# badge_mil.net
KiCad netlist of a schematic drawn in EAGLE
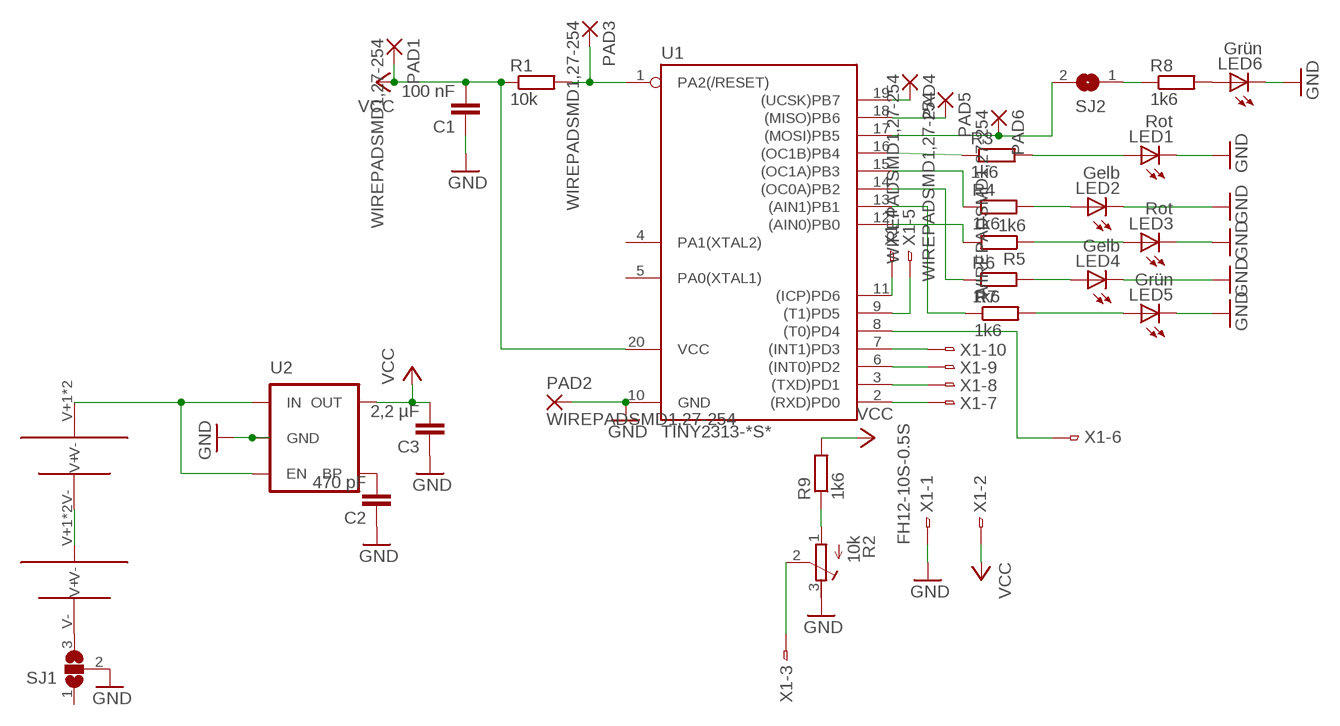
[diagram p0: schematic, sheet 1]

(export (version "E")
  (design (tool "Eeschema 10.0.6"))
  (components
    (comp (ref "C1")
      (value "100 nF")
      (footprint "eagle-import:C0805")
      (libsource (lib "eagle-import") (part "C-EUC0805"))
    )
    (comp (ref "C2")
      (value "470 pF")
      (footprint "eagle-import:C0805")
      (libsource (lib "eagle-import") (part "C-EUC0805"))
    )
    (comp (ref "C3")
      (value "2,2 µF")
      (footprint "eagle-import:C0805")
      (libsource (lib "eagle-import") (part "C-EUC0805"))
    )
    (comp (ref "LED1")
      (value "Rot")
      (footprint "eagle-import:SML0603")
      (libsource (lib "eagle-import") (part "LEDSML0603"))
    )
    (comp (ref "LED2")
      (value "Gelb")
      (footprint "eagle-import:SML0603")
      (libsource (lib "eagle-import") (part "LEDSML0603"))
    )
    (comp (ref "LED3")
      (value "Rot")
      (footprint "eagle-import:SML0603")
      (libsource (lib "eagle-import") (part "LEDSML0603"))
    )
    (comp (ref "LED4")
      (value "Gelb")
      (footprint "eagle-import:SML0603")
      (libsource (lib "eagle-import") (part "LEDSML0603"))
    )
    (comp (ref "LED5")
      (value "Grün")
      (footprint "eagle-import:SML0603")
      (libsource (lib "eagle-import") (part "LEDSML0603"))
    )
    (comp (ref "LED6")
      (value "Grün")
      (footprint "eagle-import:SML0603")
      (libsource (lib "eagle-import") (part "LEDSML0603"))
    )
    (comp (ref "PAD1")
      (value "WIREPADSMD1,27-254")
      (footprint "eagle-import:SMD1,27-2,54")
      (libsource (lib "eagle-import") (part "WIREPADSMD1,27-254"))
    )
    (comp (ref "PAD2")
      (value "WIREPADSMD1,27-254")
      (footprint "eagle-import:SMD1,27-2,54")
      (libsource (lib "eagle-import") (part "WIREPADSMD1,27-254"))
    )
    (comp (ref "PAD3")
      (value "WIREPADSMD1,27-254")
      (footprint "eagle-import:SMD1,27-2,54")
      (libsource (lib "eagle-import") (part "WIREPADSMD1,27-254"))
    )
    (comp (ref "PAD4")
      (value "WIREPADSMD1,27-254")
      (footprint "eagle-import:SMD1,27-2,54")
      (libsource (lib "eagle-import") (part "WIREPADSMD1,27-254"))
    )
    (comp (ref "PAD5")
      (value "WIREPADSMD1,27-254")
      (footprint "eagle-import:SMD1,27-2,54")
      (libsource (lib "eagle-import") (part "WIREPADSMD1,27-254"))
    )
    (comp (ref "PAD6")
      (value "WIREPADSMD1,27-254")
      (footprint "eagle-import:SMD1,27-2,54")
      (libsource (lib "eagle-import") (part "WIREPADSMD1,27-254"))
    )
    (comp (ref "R1")
      (value "10k")
      (footprint "eagle-import:R0805")
      (libsource (lib "eagle-import") (part "R-EU_R0805"))
    )
    (comp (ref "R2")
      (value "10k")
      (footprint "eagle-import:RTRIM4G_J")
      (libsource (lib "eagle-import") (part "R-TRIMM4G/J"))
    )
    (comp (ref "R3")
      (value "1k6")
      (footprint "eagle-import:R0805")
      (libsource (lib "eagle-import") (part "R-EU_R0805"))
    )
    (comp (ref "R4")
      (value "1k6")
      (footprint "eagle-import:R0805")
      (libsource (lib "eagle-import") (part "R-EU_R0805"))
    )
    (comp (ref "R5")
      (value "1k6")
      (footprint "eagle-import:R0805")
      (libsource (lib "eagle-import") (part "R-EU_R0805"))
    )
    (comp (ref "R6")
      (value "1k6")
      (footprint "eagle-import:R0805")
      (libsource (lib "eagle-import") (part "R-EU_R0805"))
    )
    (comp (ref "R7")
      (value "1k6")
      (footprint "eagle-import:R0805")
      (libsource (lib "eagle-import") (part "R-EU_R0805"))
    )
    (comp (ref "R8")
      (value "1k6")
      (footprint "eagle-import:R0805")
      (libsource (lib "eagle-import") (part "R-EU_R0805"))
    )
    (comp (ref "R9")
      (value "1k6")
      (footprint "eagle-import:R0805")
      (libsource (lib "eagle-import") (part "R-EU_R0805"))
    )
    (comp (ref "SJ1")
      (value "SJ2WW")
      (footprint "eagle-import:SJ_2W")
      (libsource (lib "eagle-import") (part "SJ2WW"))
    )
    (comp (ref "SJ2")
      (value "SJW")
      (footprint "eagle-import:SJW")
      (libsource (lib "eagle-import") (part "SJW"))
    )
    (comp (ref "U$1")
      (value "KEYSTONE3002")
      (footprint "eagle-import:KEYSTONE3002")
      (libsource (lib "eagle-import") (part "KEYSTONE3002"))
    )
    (comp (ref "U$2")
      (value "KEYSTONE3002")
      (footprint "eagle-import:KEYSTONE3002")
      (libsource (lib "eagle-import") (part "KEYSTONE3002"))
    )
    (comp (ref "U1")
      (value "TINY2313-*S*")
      (footprint "eagle-import:SO20L$")
      (libsource (lib "eagle-import") (part "TINY2313-S"))
    )
    (comp (ref "U2")
      (value "MIC52055V")
      (footprint "eagle-import:SOT23-5")
      (libsource (lib "eagle-import") (part "MIC52055V"))
    )
    (comp (ref "X1")
      (value "FH12-10S-0.5S")
      (footprint "eagle-import:FH12-10S-1.0SH")
      (libsource (lib "eagle-import") (part "FH12-10S-0.5S"))
    )
  )
  (nets
    (net (code "1") (name "GND") (class "Default")
      (node (ref "C1") (pin "1") (pinfunction "1_1") (pintype "passive"))
      (node (ref "C2") (pin "1") (pinfunction "1_1") (pintype "passive"))
      (node (ref "C3") (pin "1") (pinfunction "1_1") (pintype "passive"))
      (node (ref "LED1") (pin "C") (pinfunction "C_C") (pintype "passive"))
      (node (ref "LED2") (pin "C") (pinfunction "C_C") (pintype "passive"))
      (node (ref "LED3") (pin "C") (pinfunction "C_C") (pintype "passive"))
      (node (ref "LED4") (pin "C") (pinfunction "C_C") (pintype "passive"))
      (node (ref "LED5") (pin "C") (pinfunction "C_C") (pintype "passive"))
      (node (ref "LED6") (pin "C") (pinfunction "C_C") (pintype "passive"))
      (node (ref "PAD2") (pin "1") (pinfunction "P_1") (pintype "passive"))
      (node (ref "R2") (pin "3") (pinfunction "A_3") (pintype "passive"))
      (node (ref "SJ1") (pin "2") (pinfunction "2_2") (pintype "passive"))
      (node (ref "U1") (pin "10") (pinfunction "GND_10") (pintype "power_in"))
      (node (ref "U2") (pin "2") (pinfunction "GND_2") (pintype "input"))
      (node (ref "X1") (pin "1") (pinfunction "1_1") (pintype "passive"))
    )
    (net (code "2") (name "Net-(LED1-PadA)") (class "Default")
      (node (ref "LED1") (pin "A") (pinfunction "A_A") (pintype "passive"))
      (node (ref "R3") (pin "2") (pinfunction "2_2") (pintype "passive"))
    )
    (net (code "3") (name "Net-(LED2-PadA)") (class "Default")
      (node (ref "LED2") (pin "A") (pinfunction "A_A") (pintype "passive"))
      (node (ref "R4") (pin "2") (pinfunction "2_2") (pintype "passive"))
    )
    (net (code "4") (name "Net-(LED3-PadA)") (class "Default")
      (node (ref "LED3") (pin "A") (pinfunction "A_A") (pintype "passive"))
      (node (ref "R5") (pin "1") (pinfunction "1_1") (pintype "passive"))
    )
    (net (code "5") (name "Net-(LED4-PadA)") (class "Default")
      (node (ref "LED4") (pin "A") (pinfunction "A_A") (pintype "passive"))
      (node (ref "R6") (pin "2") (pinfunction "2_2") (pintype "passive"))
    )
    (net (code "6") (name "Net-(LED5-PadA)") (class "Default")
      (node (ref "LED5") (pin "A") (pinfunction "A_A") (pintype "passive"))
      (node (ref "R7") (pin "2") (pinfunction "2_2") (pintype "passive"))
    )
    (net (code "7") (name "Net-(LED6-PadA)") (class "Default")
      (node (ref "LED6") (pin "A") (pinfunction "A_A") (pintype "passive"))
      (node (ref "R8") (pin "2") (pinfunction "2_2") (pintype "passive"))
    )
    (net (code "8") (name "Net-(PAD3-P)") (class "Default")
      (node (ref "PAD3") (pin "1") (pinfunction "P_1") (pintype "passive"))
      (node (ref "R1") (pin "2") (pinfunction "2_2") (pintype "passive"))
      (node (ref "U1") (pin "1") (pinfunction "PA2(/RESET)_1") (pintype "input"))
    )
    (net (code "9") (name "Net-(PAD4-P)") (class "Default")
      (node (ref "PAD4") (pin "1") (pinfunction "P_1") (pintype "passive"))
      (node (ref "U1") (pin "19") (pinfunction "(UCSK)PB7_19") (pintype "bidirectional"))
    )
    (net (code "10") (name "Net-(PAD5-P)") (class "Default")
      (node (ref "PAD5") (pin "1") (pinfunction "P_1") (pintype "passive"))
      (node (ref "U1") (pin "18") (pinfunction "(MISO)PB6_18") (pintype "bidirectional"))
    )
    (net (code "11") (name "Net-(PAD6-P)") (class "Default")
      (node (ref "PAD6") (pin "1") (pinfunction "P_1") (pintype "passive"))
      (node (ref "SJ2") (pin "2") (pinfunction "2_2") (pintype "passive"))
      (node (ref "U1") (pin "17") (pinfunction "(MOSI)PB5_17") (pintype "bidirectional"))
    )
    (net (code "12") (name "Net-(R2-E)") (class "Default")
      (node (ref "R2") (pin "1") (pinfunction "E_1") (pintype "passive"))
      (node (ref "R9") (pin "1") (pinfunction "1_1") (pintype "passive"))
    )
    (net (code "13") (name "Net-(R2-S)") (class "Default")
      (node (ref "R2") (pin "2") (pinfunction "S_2") (pintype "passive"))
      (node (ref "X1") (pin "3") (pinfunction "1_3") (pintype "passive"))
    )
    (net (code "14") (name "Net-(R8-Pad1)") (class "Default")
      (node (ref "R8") (pin "1") (pinfunction "1_1") (pintype "passive"))
      (node (ref "SJ2") (pin "1") (pinfunction "1_1") (pintype "passive"))
    )
    (net (code "15") (name "Net-(SJ1-Pad3)") (class "Default")
      (node (ref "SJ1") (pin "3") (pinfunction "3_3") (pintype "passive"))
      (node (ref "U$2") (pin "V-") (pinfunction "V-_V-") (pintype "bidirectional"))
    )
    (net (code "16") (name "Net-(U$1-PadV-)") (class "Default")
      (node (ref "U$1") (pin "V-") (pinfunction "V-_V-") (pintype "bidirectional"))
      (node (ref "U$2") (pin "V+1") (pinfunction "V+_V+1") (pintype "bidirectional"))
      (node (ref "U$2") (pin "V+2") (pinfunction "V+_V+2") (pintype "bidirectional"))
    )
    (net (code "17") (name "Net-(U1-(AIN0)PB0)") (class "Default")
      (node (ref "R5") (pin "2") (pinfunction "2_2") (pintype "passive"))
      (node (ref "U1") (pin "12") (pinfunction "(AIN0)PB0_12") (pintype "bidirectional"))
    )
    (net (code "18") (name "Net-(U1-(AIN1)PB1)") (class "Default")
      (node (ref "R7") (pin "1") (pinfunction "1_1") (pintype "passive"))
      (node (ref "U1") (pin "13") (pinfunction "(AIN1)PB1_13") (pintype "bidirectional"))
    )
    (net (code "19") (name "Net-(U1-(ICP)PD6)") (class "Default")
      (node (ref "U1") (pin "11") (pinfunction "(ICP)PD6_11") (pintype "bidirectional"))
      (node (ref "X1") (pin "4") (pinfunction "1_4") (pintype "passive"))
    )
    (net (code "20") (name "Net-(U1-(INT0)PD2)") (class "Default")
      (node (ref "U1") (pin "6") (pinfunction "(INT0)PD2_6") (pintype "bidirectional"))
      (node (ref "X1") (pin "9") (pinfunction "1_9") (pintype "passive"))
    )
    (net (code "21") (name "Net-(U1-(INT1)PD3)") (class "Default")
      (node (ref "U1") (pin "7") (pinfunction "(INT1)PD3_7") (pintype "bidirectional"))
      (node (ref "X1") (pin "10") (pinfunction "1_10") (pintype "passive"))
    )
    (net (code "22") (name "Net-(U1-(OC0A)PB2)") (class "Default")
      (node (ref "R6") (pin "1") (pinfunction "1_1") (pintype "passive"))
      (node (ref "U1") (pin "14") (pinfunction "(OC0A)PB2_14") (pintype "bidirectional"))
    )
    (net (code "23") (name "Net-(U1-(OC1A)PB3)") (class "Default")
      (node (ref "R4") (pin "1") (pinfunction "1_1") (pintype "passive"))
      (node (ref "U1") (pin "15") (pinfunction "(OC1A)PB3_15") (pintype "bidirectional"))
    )
    (net (code "24") (name "Net-(U1-(OC1B)PB4)") (class "Default")
      (node (ref "R3") (pin "1") (pinfunction "1_1") (pintype "passive"))
      (node (ref "U1") (pin "16") (pinfunction "(OC1B)PB4_16") (pintype "bidirectional"))
    )
    (net (code "25") (name "Net-(U1-(RXD)PD0)") (class "Default")
      (node (ref "U1") (pin "2") (pinfunction "(RXD)PD0_2") (pintype "bidirectional"))
      (node (ref "X1") (pin "7") (pinfunction "1_7") (pintype "passive"))
    )
    (net (code "26") (name "Net-(U1-(T0)PD4)") (class "Default")
      (node (ref "U1") (pin "8") (pinfunction "(T0)PD4_8") (pintype "bidirectional"))
      (node (ref "X1") (pin "6") (pinfunction "1_6") (pintype "passive"))
    )
    (net (code "27") (name "Net-(U1-(T1)PD5)") (class "Default")
      (node (ref "U1") (pin "9") (pinfunction "(T1)PD5_9") (pintype "bidirectional"))
      (node (ref "X1") (pin "5") (pinfunction "1_5") (pintype "passive"))
    )
    (net (code "28") (name "Net-(U1-(TXD)PD1)") (class "Default")
      (node (ref "U1") (pin "3") (pinfunction "(TXD)PD1_3") (pintype "bidirectional"))
      (node (ref "X1") (pin "8") (pinfunction "1_8") (pintype "passive"))
    )
    (net (code "29") (name "Net-(U2-BP)") (class "Default")
      (node (ref "C2") (pin "2") (pinfunction "2_2") (pintype "passive"))
      (node (ref "U2") (pin "4") (pinfunction "BP_4") (pintype "input"))
    )
    (net (code "30") (name "Net-(U2-EN)") (class "Default")
      (node (ref "U$1") (pin "V+1") (pinfunction "V+_V+1") (pintype "bidirectional"))
      (node (ref "U$1") (pin "V+2") (pinfunction "V+_V+2") (pintype "bidirectional"))
      (node (ref "U2") (pin "1") (pinfunction "IN_1") (pintype "input"))
      (node (ref "U2") (pin "3") (pinfunction "EN_3") (pintype "input"))
    )
    (net (code "31") (name "VCC") (class "Default")
      (node (ref "C1") (pin "2") (pinfunction "2_2") (pintype "passive"))
      (node (ref "C3") (pin "2") (pinfunction "2_2") (pintype "passive"))
      (node (ref "PAD1") (pin "1") (pinfunction "P_1") (pintype "passive"))
      (node (ref "R1") (pin "1") (pinfunction "1_1") (pintype "passive"))
      (node (ref "R9") (pin "2") (pinfunction "2_2") (pintype "passive"))
      (node (ref "U1") (pin "20") (pinfunction "VCC_20") (pintype "power_in"))
      (node (ref "U2") (pin "5") (pinfunction "OUT_5") (pintype "passive"))
      (node (ref "X1") (pin "2") (pinfunction "1_2") (pintype "passive"))
    )
    (net (code "32") (name "unconnected-(SJ1-Pad1)") (class "Default")
      (node (ref "SJ1") (pin "1") (pinfunction "1_1") (pintype "passive"))
    )
    (net (code "33") (name "unconnected-(U1-PA0(XTAL1)-Pad5)") (class "Default")
      (node (ref "U1") (pin "5") (pinfunction "PA0(XTAL1)_5") (pintype "bidirectional"))
    )
    (net (code "34") (name "unconnected-(U1-PA1(XTAL2)-Pad4)") (class "Default")
      (node (ref "U1") (pin "4") (pinfunction "PA1(XTAL2)_4") (pintype "bidirectional"))
    )
  )
)
